# shift_register.net
KiCad netlist of a schematic drawn in EAGLE
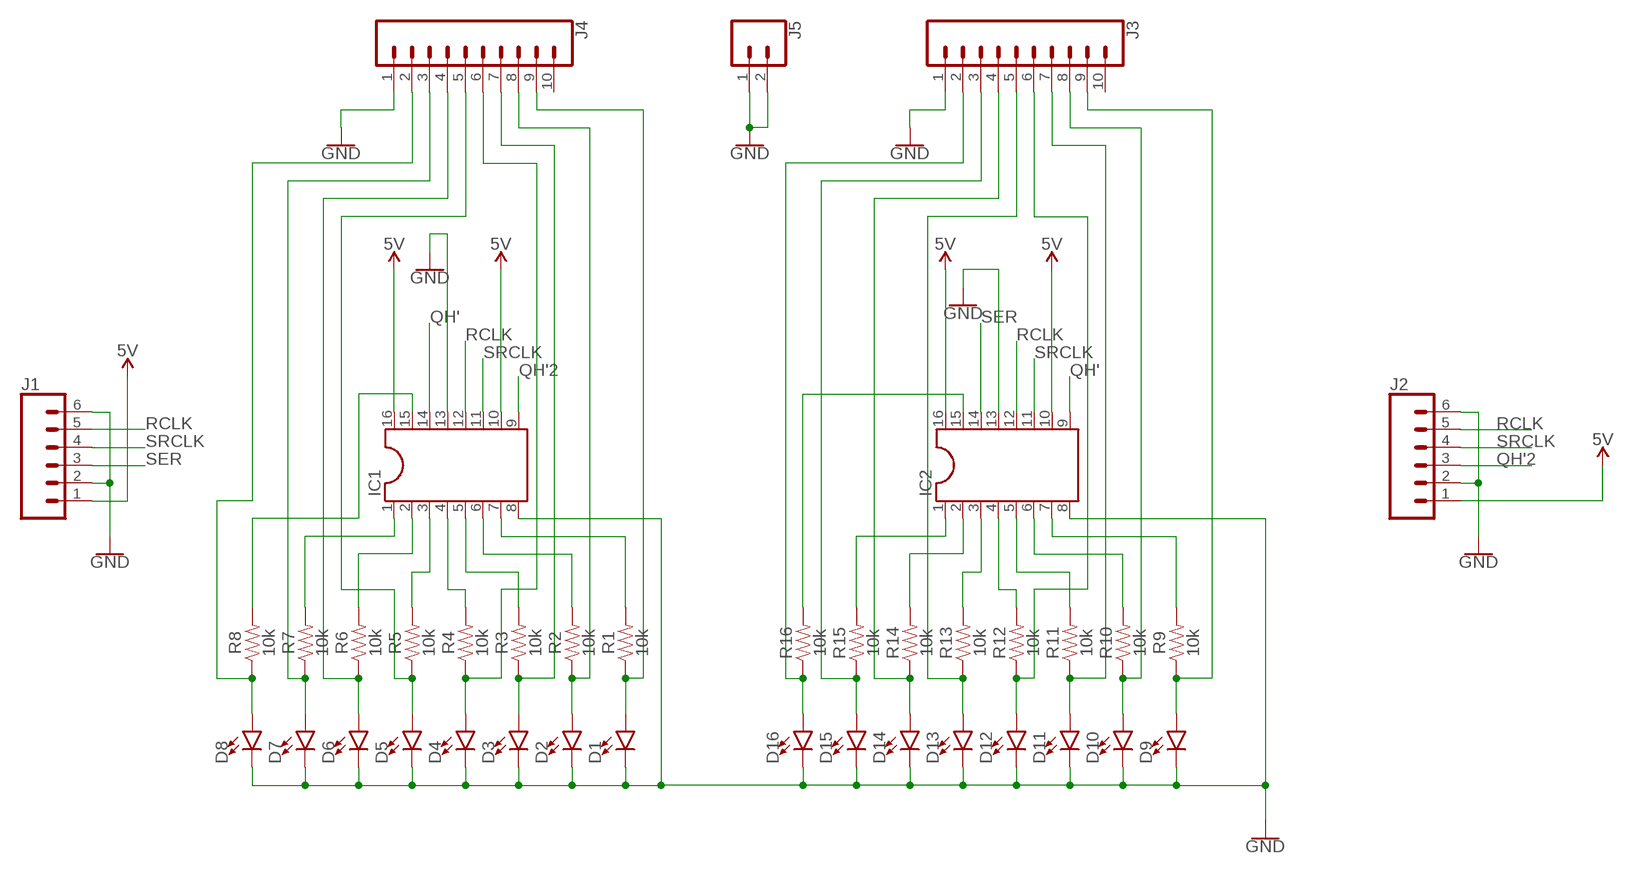
[diagram p0: schematic, sheet 1]

(export (version "E")
  (design (tool "Eeschema 10.0.6"))
  (components
    (comp (ref "D1")
      (value "LED3MM")
      (footprint "eagle-import:LED_3MM")
      (libsource (lib "eagle-import") (part "LED3MM"))
    )
    (comp (ref "D2")
      (value "LED3MM")
      (footprint "eagle-import:LED_3MM")
      (libsource (lib "eagle-import") (part "LED3MM"))
    )
    (comp (ref "D3")
      (value "LED3MM")
      (footprint "eagle-import:LED_3MM")
      (libsource (lib "eagle-import") (part "LED3MM"))
    )
    (comp (ref "D4")
      (value "LED3MM")
      (footprint "eagle-import:LED_3MM")
      (libsource (lib "eagle-import") (part "LED3MM"))
    )
    (comp (ref "D5")
      (value "LED3MM")
      (footprint "eagle-import:LED_3MM")
      (libsource (lib "eagle-import") (part "LED3MM"))
    )
    (comp (ref "D6")
      (value "LED3MM")
      (footprint "eagle-import:LED_3MM")
      (libsource (lib "eagle-import") (part "LED3MM"))
    )
    (comp (ref "D7")
      (value "LED3MM")
      (footprint "eagle-import:LED_3MM")
      (libsource (lib "eagle-import") (part "LED3MM"))
    )
    (comp (ref "D8")
      (value "LED3MM")
      (footprint "eagle-import:LED_3MM")
      (libsource (lib "eagle-import") (part "LED3MM"))
    )
    (comp (ref "D9")
      (value "LED3MM")
      (footprint "eagle-import:LED_3MM")
      (libsource (lib "eagle-import") (part "LED3MM"))
    )
    (comp (ref "D10")
      (value "LED3MM")
      (footprint "eagle-import:LED_3MM")
      (libsource (lib "eagle-import") (part "LED3MM"))
    )
    (comp (ref "D11")
      (value "LED3MM")
      (footprint "eagle-import:LED_3MM")
      (libsource (lib "eagle-import") (part "LED3MM"))
    )
    (comp (ref "D12")
      (value "LED3MM")
      (footprint "eagle-import:LED_3MM")
      (libsource (lib "eagle-import") (part "LED3MM"))
    )
    (comp (ref "D13")
      (value "LED3MM")
      (footprint "eagle-import:LED_3MM")
      (libsource (lib "eagle-import") (part "LED3MM"))
    )
    (comp (ref "D14")
      (value "LED3MM")
      (footprint "eagle-import:LED_3MM")
      (libsource (lib "eagle-import") (part "LED3MM"))
    )
    (comp (ref "D15")
      (value "LED3MM")
      (footprint "eagle-import:LED_3MM")
      (libsource (lib "eagle-import") (part "LED3MM"))
    )
    (comp (ref "D16")
      (value "LED3MM")
      (footprint "eagle-import:LED_3MM")
      (libsource (lib "eagle-import") (part "LED3MM"))
    )
    (comp (ref "IC1")
      (value "DIL16")
      (footprint "eagle-import:DIL16")
      (libsource (lib "eagle-import") (part "DIL16"))
    )
    (comp (ref "IC2")
      (value "DIL16")
      (footprint "eagle-import:DIL16")
      (libsource (lib "eagle-import") (part "DIL16"))
    )
    (comp (ref "J1")
      (value "CONN_06SILK_FEMALE_PTH")
      (footprint "eagle-import:1X06")
      (libsource (lib "eagle-import") (part "CONN_06SILK_FEMALE_PTH"))
    )
    (comp (ref "J2")
      (value "CONN_06SILK_FEMALE_PTH")
      (footprint "eagle-import:1X06")
      (libsource (lib "eagle-import") (part "CONN_06SILK_FEMALE_PTH"))
    )
    (comp (ref "J3")
      (value "CONN_10\"")
      (footprint "eagle-import:1X10")
      (libsource (lib "eagle-import") (part "CONN_10{dblquote}"))
    )
    (comp (ref "J4")
      (value "CONN_10\"")
      (footprint "eagle-import:1X10")
      (libsource (lib "eagle-import") (part "CONN_10{dblquote}"))
    )
    (comp (ref "J5")
      (value "CONN_02")
      (footprint "eagle-import:1X02")
      (libsource (lib "eagle-import") (part "CONN_02"))
    )
    (comp (ref "R1")
      (value "10k")
      (footprint "eagle-import:AXIAL-0.3")
      (libsource (lib "eagle-import") (part "10KOHM-HORIZ-1/6W-5%"))
    )
    (comp (ref "R2")
      (value "10k")
      (footprint "eagle-import:AXIAL-0.3")
      (libsource (lib "eagle-import") (part "10KOHM-HORIZ-1/6W-5%"))
    )
    (comp (ref "R3")
      (value "10k")
      (footprint "eagle-import:AXIAL-0.3")
      (libsource (lib "eagle-import") (part "10KOHM-HORIZ-1/6W-5%"))
    )
    (comp (ref "R4")
      (value "10k")
      (footprint "eagle-import:AXIAL-0.3")
      (libsource (lib "eagle-import") (part "10KOHM-HORIZ-1/6W-5%"))
    )
    (comp (ref "R5")
      (value "10k")
      (footprint "eagle-import:AXIAL-0.3")
      (libsource (lib "eagle-import") (part "10KOHM-HORIZ-1/6W-5%"))
    )
    (comp (ref "R6")
      (value "10k")
      (footprint "eagle-import:AXIAL-0.3")
      (libsource (lib "eagle-import") (part "10KOHM-HORIZ-1/6W-5%"))
    )
    (comp (ref "R7")
      (value "10k")
      (footprint "eagle-import:AXIAL-0.3")
      (libsource (lib "eagle-import") (part "10KOHM-HORIZ-1/6W-5%"))
    )
    (comp (ref "R8")
      (value "10k")
      (footprint "eagle-import:AXIAL-0.3")
      (libsource (lib "eagle-import") (part "10KOHM-HORIZ-1/6W-5%"))
    )
    (comp (ref "R9")
      (value "10k")
      (footprint "eagle-import:AXIAL-0.3")
      (libsource (lib "eagle-import") (part "10KOHM-HORIZ-1/6W-5%"))
    )
    (comp (ref "R10")
      (value "10k")
      (footprint "eagle-import:AXIAL-0.3")
      (libsource (lib "eagle-import") (part "10KOHM-HORIZ-1/6W-5%"))
    )
    (comp (ref "R11")
      (value "10k")
      (footprint "eagle-import:AXIAL-0.3")
      (libsource (lib "eagle-import") (part "10KOHM-HORIZ-1/6W-5%"))
    )
    (comp (ref "R12")
      (value "10k")
      (footprint "eagle-import:AXIAL-0.3")
      (libsource (lib "eagle-import") (part "10KOHM-HORIZ-1/6W-5%"))
    )
    (comp (ref "R13")
      (value "10k")
      (footprint "eagle-import:AXIAL-0.3")
      (libsource (lib "eagle-import") (part "10KOHM-HORIZ-1/6W-5%"))
    )
    (comp (ref "R14")
      (value "10k")
      (footprint "eagle-import:AXIAL-0.3")
      (libsource (lib "eagle-import") (part "10KOHM-HORIZ-1/6W-5%"))
    )
    (comp (ref "R15")
      (value "10k")
      (footprint "eagle-import:AXIAL-0.3")
      (libsource (lib "eagle-import") (part "10KOHM-HORIZ-1/6W-5%"))
    )
    (comp (ref "R16")
      (value "10k")
      (footprint "eagle-import:AXIAL-0.3")
      (libsource (lib "eagle-import") (part "10KOHM-HORIZ-1/6W-5%"))
    )
  )
  (nets
    (net (code "1") (name "/QH'") (class "Default")
      (node (ref "IC1") (pin "14") (pinfunction "14_14") (pintype "passive"))
      (node (ref "IC2") (pin "9") (pinfunction "9_9") (pintype "passive"))
    )
    (net (code "2") (name "/QH'2") (class "Default")
      (node (ref "IC1") (pin "9") (pinfunction "9_9") (pintype "passive"))
      (node (ref "J2") (pin "3") (pinfunction "3_3") (pintype "passive"))
    )
    (net (code "3") (name "/RCLK") (class "Default")
      (node (ref "IC1") (pin "12") (pinfunction "12_12") (pintype "passive"))
      (node (ref "IC2") (pin "12") (pinfunction "12_12") (pintype "passive"))
      (node (ref "J1") (pin "5") (pinfunction "5_5") (pintype "passive"))
      (node (ref "J2") (pin "5") (pinfunction "5_5") (pintype "passive"))
    )
    (net (code "4") (name "/SER") (class "Default")
      (node (ref "IC2") (pin "14") (pinfunction "14_14") (pintype "passive"))
      (node (ref "J1") (pin "3") (pinfunction "3_3") (pintype "passive"))
    )
    (net (code "5") (name "/SRCLK") (class "Default")
      (node (ref "IC1") (pin "11") (pinfunction "11_11") (pintype "passive"))
      (node (ref "IC2") (pin "11") (pinfunction "11_11") (pintype "passive"))
      (node (ref "J1") (pin "4") (pinfunction "4_4") (pintype "passive"))
      (node (ref "J2") (pin "4") (pinfunction "4_4") (pintype "passive"))
    )
    (net (code "6") (name "5V") (class "Default")
      (node (ref "IC1") (pin "10") (pinfunction "10_10") (pintype "passive"))
      (node (ref "IC1") (pin "16") (pinfunction "16_16") (pintype "passive"))
      (node (ref "IC2") (pin "10") (pinfunction "10_10") (pintype "passive"))
      (node (ref "IC2") (pin "16") (pinfunction "16_16") (pintype "passive"))
      (node (ref "J1") (pin "1") (pinfunction "1_1") (pintype "passive"))
      (node (ref "J2") (pin "1") (pinfunction "1_1") (pintype "passive"))
    )
    (net (code "7") (name "GND") (class "Default")
      (node (ref "D1") (pin "K") (pinfunction "C_K") (pintype "passive"))
      (node (ref "D10") (pin "K") (pinfunction "C_K") (pintype "passive"))
      (node (ref "D11") (pin "K") (pinfunction "C_K") (pintype "passive"))
      (node (ref "D12") (pin "K") (pinfunction "C_K") (pintype "passive"))
      (node (ref "D13") (pin "K") (pinfunction "C_K") (pintype "passive"))
      (node (ref "D14") (pin "K") (pinfunction "C_K") (pintype "passive"))
      (node (ref "D15") (pin "K") (pinfunction "C_K") (pintype "passive"))
      (node (ref "D16") (pin "K") (pinfunction "C_K") (pintype "passive"))
      (node (ref "D2") (pin "K") (pinfunction "C_K") (pintype "passive"))
      (node (ref "D3") (pin "K") (pinfunction "C_K") (pintype "passive"))
      (node (ref "D4") (pin "K") (pinfunction "C_K") (pintype "passive"))
      (node (ref "D5") (pin "K") (pinfunction "C_K") (pintype "passive"))
      (node (ref "D6") (pin "K") (pinfunction "C_K") (pintype "passive"))
      (node (ref "D7") (pin "K") (pinfunction "C_K") (pintype "passive"))
      (node (ref "D8") (pin "K") (pinfunction "C_K") (pintype "passive"))
      (node (ref "D9") (pin "K") (pinfunction "C_K") (pintype "passive"))
      (node (ref "IC1") (pin "13") (pinfunction "13_13") (pintype "passive"))
      (node (ref "IC1") (pin "8") (pinfunction "8_8") (pintype "passive"))
      (node (ref "IC2") (pin "13") (pinfunction "13_13") (pintype "passive"))
      (node (ref "IC2") (pin "8") (pinfunction "8_8") (pintype "passive"))
      (node (ref "J1") (pin "2") (pinfunction "2_2") (pintype "passive"))
      (node (ref "J1") (pin "6") (pinfunction "6_6") (pintype "passive"))
      (node (ref "J2") (pin "2") (pinfunction "2_2") (pintype "passive"))
      (node (ref "J2") (pin "6") (pinfunction "6_6") (pintype "passive"))
      (node (ref "J3") (pin "1") (pinfunction "1_1") (pintype "passive"))
      (node (ref "J4") (pin "1") (pinfunction "1_1") (pintype "passive"))
      (node (ref "J5") (pin "1") (pinfunction "1_1") (pintype "passive"))
      (node (ref "J5") (pin "2") (pinfunction "2_2") (pintype "passive"))
    )
    (net (code "8") (name "Net-(R1-1)") (class "Default")
      (node (ref "D1") (pin "A") (pinfunction "A_A") (pintype "passive"))
      (node (ref "J4") (pin "9") (pinfunction "9_9") (pintype "passive"))
      (node (ref "R1") (pin "P$1") (pinfunction "1_P$1") (pintype "passive"))
    )
    (net (code "9") (name "Net-(R1-2)") (class "Default")
      (node (ref "IC1") (pin "7") (pinfunction "7_7") (pintype "passive"))
      (node (ref "R1") (pin "P$2") (pinfunction "2_P$2") (pintype "passive"))
    )
    (net (code "10") (name "Net-(R2-1)") (class "Default")
      (node (ref "D2") (pin "A") (pinfunction "A_A") (pintype "passive"))
      (node (ref "J4") (pin "8") (pinfunction "8_8") (pintype "passive"))
      (node (ref "R2") (pin "P$1") (pinfunction "1_P$1") (pintype "passive"))
    )
    (net (code "11") (name "Net-(R2-2)") (class "Default")
      (node (ref "IC1") (pin "6") (pinfunction "6_6") (pintype "passive"))
      (node (ref "R2") (pin "P$2") (pinfunction "2_P$2") (pintype "passive"))
    )
    (net (code "12") (name "Net-(R3-1)") (class "Default")
      (node (ref "D3") (pin "A") (pinfunction "A_A") (pintype "passive"))
      (node (ref "J4") (pin "7") (pinfunction "7_7") (pintype "passive"))
      (node (ref "R3") (pin "P$1") (pinfunction "1_P$1") (pintype "passive"))
    )
    (net (code "13") (name "Net-(R3-2)") (class "Default")
      (node (ref "IC1") (pin "5") (pinfunction "5_5") (pintype "passive"))
      (node (ref "R3") (pin "P$2") (pinfunction "2_P$2") (pintype "passive"))
    )
    (net (code "14") (name "Net-(R4-1)") (class "Default")
      (node (ref "D4") (pin "A") (pinfunction "A_A") (pintype "passive"))
      (node (ref "J4") (pin "6") (pinfunction "6_6") (pintype "passive"))
      (node (ref "R4") (pin "P$1") (pinfunction "1_P$1") (pintype "passive"))
    )
    (net (code "15") (name "Net-(R4-2)") (class "Default")
      (node (ref "IC1") (pin "4") (pinfunction "4_4") (pintype "passive"))
      (node (ref "R4") (pin "P$2") (pinfunction "2_P$2") (pintype "passive"))
    )
    (net (code "16") (name "Net-(R5-1)") (class "Default")
      (node (ref "D5") (pin "A") (pinfunction "A_A") (pintype "passive"))
      (node (ref "J4") (pin "5") (pinfunction "5_5") (pintype "passive"))
      (node (ref "R5") (pin "P$1") (pinfunction "1_P$1") (pintype "passive"))
    )
    (net (code "17") (name "Net-(R5-2)") (class "Default")
      (node (ref "IC1") (pin "3") (pinfunction "3_3") (pintype "passive"))
      (node (ref "R5") (pin "P$2") (pinfunction "2_P$2") (pintype "passive"))
    )
    (net (code "18") (name "Net-(R6-1)") (class "Default")
      (node (ref "D6") (pin "A") (pinfunction "A_A") (pintype "passive"))
      (node (ref "J4") (pin "4") (pinfunction "4_4") (pintype "passive"))
      (node (ref "R6") (pin "P$1") (pinfunction "1_P$1") (pintype "passive"))
    )
    (net (code "19") (name "Net-(R6-2)") (class "Default")
      (node (ref "IC1") (pin "2") (pinfunction "2_2") (pintype "passive"))
      (node (ref "R6") (pin "P$2") (pinfunction "2_P$2") (pintype "passive"))
    )
    (net (code "20") (name "Net-(R7-1)") (class "Default")
      (node (ref "D7") (pin "A") (pinfunction "A_A") (pintype "passive"))
      (node (ref "J4") (pin "3") (pinfunction "3_3") (pintype "passive"))
      (node (ref "R7") (pin "P$1") (pinfunction "1_P$1") (pintype "passive"))
    )
    (net (code "21") (name "Net-(R7-2)") (class "Default")
      (node (ref "IC1") (pin "1") (pinfunction "1_1") (pintype "passive"))
      (node (ref "R7") (pin "P$2") (pinfunction "2_P$2") (pintype "passive"))
    )
    (net (code "22") (name "Net-(R8-1)") (class "Default")
      (node (ref "D8") (pin "A") (pinfunction "A_A") (pintype "passive"))
      (node (ref "J4") (pin "2") (pinfunction "2_2") (pintype "passive"))
      (node (ref "R8") (pin "P$1") (pinfunction "1_P$1") (pintype "passive"))
    )
    (net (code "23") (name "Net-(R8-2)") (class "Default")
      (node (ref "IC1") (pin "15") (pinfunction "15_15") (pintype "passive"))
      (node (ref "R8") (pin "P$2") (pinfunction "2_P$2") (pintype "passive"))
    )
    (net (code "24") (name "Net-(R9-1)") (class "Default")
      (node (ref "D9") (pin "A") (pinfunction "A_A") (pintype "passive"))
      (node (ref "J3") (pin "9") (pinfunction "9_9") (pintype "passive"))
      (node (ref "R9") (pin "P$1") (pinfunction "1_P$1") (pintype "passive"))
    )
    (net (code "25") (name "Net-(R9-2)") (class "Default")
      (node (ref "IC2") (pin "7") (pinfunction "7_7") (pintype "passive"))
      (node (ref "R9") (pin "P$2") (pinfunction "2_P$2") (pintype "passive"))
    )
    (net (code "26") (name "Net-(R10-1)") (class "Default")
      (node (ref "D10") (pin "A") (pinfunction "A_A") (pintype "passive"))
      (node (ref "J3") (pin "8") (pinfunction "8_8") (pintype "passive"))
      (node (ref "R10") (pin "P$1") (pinfunction "1_P$1") (pintype "passive"))
    )
    (net (code "27") (name "Net-(R10-2)") (class "Default")
      (node (ref "IC2") (pin "6") (pinfunction "6_6") (pintype "passive"))
      (node (ref "R10") (pin "P$2") (pinfunction "2_P$2") (pintype "passive"))
    )
    (net (code "28") (name "Net-(R11-1)") (class "Default")
      (node (ref "D11") (pin "A") (pinfunction "A_A") (pintype "passive"))
      (node (ref "J3") (pin "7") (pinfunction "7_7") (pintype "passive"))
      (node (ref "R11") (pin "P$1") (pinfunction "1_P$1") (pintype "passive"))
    )
    (net (code "29") (name "Net-(R11-2)") (class "Default")
      (node (ref "IC2") (pin "5") (pinfunction "5_5") (pintype "passive"))
      (node (ref "R11") (pin "P$2") (pinfunction "2_P$2") (pintype "passive"))
    )
    (net (code "30") (name "Net-(R12-1)") (class "Default")
      (node (ref "D12") (pin "A") (pinfunction "A_A") (pintype "passive"))
      (node (ref "J3") (pin "6") (pinfunction "6_6") (pintype "passive"))
      (node (ref "R12") (pin "P$1") (pinfunction "1_P$1") (pintype "passive"))
    )
    (net (code "31") (name "Net-(R12-2)") (class "Default")
      (node (ref "IC2") (pin "4") (pinfunction "4_4") (pintype "passive"))
      (node (ref "R12") (pin "P$2") (pinfunction "2_P$2") (pintype "passive"))
    )
    (net (code "32") (name "Net-(R13-1)") (class "Default")
      (node (ref "D13") (pin "A") (pinfunction "A_A") (pintype "passive"))
      (node (ref "J3") (pin "5") (pinfunction "5_5") (pintype "passive"))
      (node (ref "R13") (pin "P$1") (pinfunction "1_P$1") (pintype "passive"))
    )
    (net (code "33") (name "Net-(R13-2)") (class "Default")
      (node (ref "IC2") (pin "3") (pinfunction "3_3") (pintype "passive"))
      (node (ref "R13") (pin "P$2") (pinfunction "2_P$2") (pintype "passive"))
    )
    (net (code "34") (name "Net-(R14-1)") (class "Default")
      (node (ref "D14") (pin "A") (pinfunction "A_A") (pintype "passive"))
      (node (ref "J3") (pin "4") (pinfunction "4_4") (pintype "passive"))
      (node (ref "R14") (pin "P$1") (pinfunction "1_P$1") (pintype "passive"))
    )
    (net (code "35") (name "Net-(R14-2)") (class "Default")
      (node (ref "IC2") (pin "2") (pinfunction "2_2") (pintype "passive"))
      (node (ref "R14") (pin "P$2") (pinfunction "2_P$2") (pintype "passive"))
    )
    (net (code "36") (name "Net-(R15-1)") (class "Default")
      (node (ref "D15") (pin "A") (pinfunction "A_A") (pintype "passive"))
      (node (ref "J3") (pin "3") (pinfunction "3_3") (pintype "passive"))
      (node (ref "R15") (pin "P$1") (pinfunction "1_P$1") (pintype "passive"))
    )
    (net (code "37") (name "Net-(R15-2)") (class "Default")
      (node (ref "IC2") (pin "1") (pinfunction "1_1") (pintype "passive"))
      (node (ref "R15") (pin "P$2") (pinfunction "2_P$2") (pintype "passive"))
    )
    (net (code "38") (name "Net-(R16-1)") (class "Default")
      (node (ref "D16") (pin "A") (pinfunction "A_A") (pintype "passive"))
      (node (ref "J3") (pin "2") (pinfunction "2_2") (pintype "passive"))
      (node (ref "R16") (pin "P$1") (pinfunction "1_P$1") (pintype "passive"))
    )
    (net (code "39") (name "Net-(R16-2)") (class "Default")
      (node (ref "IC2") (pin "15") (pinfunction "15_15") (pintype "passive"))
      (node (ref "R16") (pin "P$2") (pinfunction "2_P$2") (pintype "passive"))
    )
    (net (code "40") (name "unconnected-(J3-Pad10)") (class "Default")
      (node (ref "J3") (pin "10") (pinfunction "10_10") (pintype "passive"))
    )
    (net (code "41") (name "unconnected-(J4-Pad10)") (class "Default")
      (node (ref "J4") (pin "10") (pinfunction "10_10") (pintype "passive"))
    )
  )
)
